# SCH_usb-hub_2024-06-19.net
KiCad netlist of a schematic drawn in EasyEDA
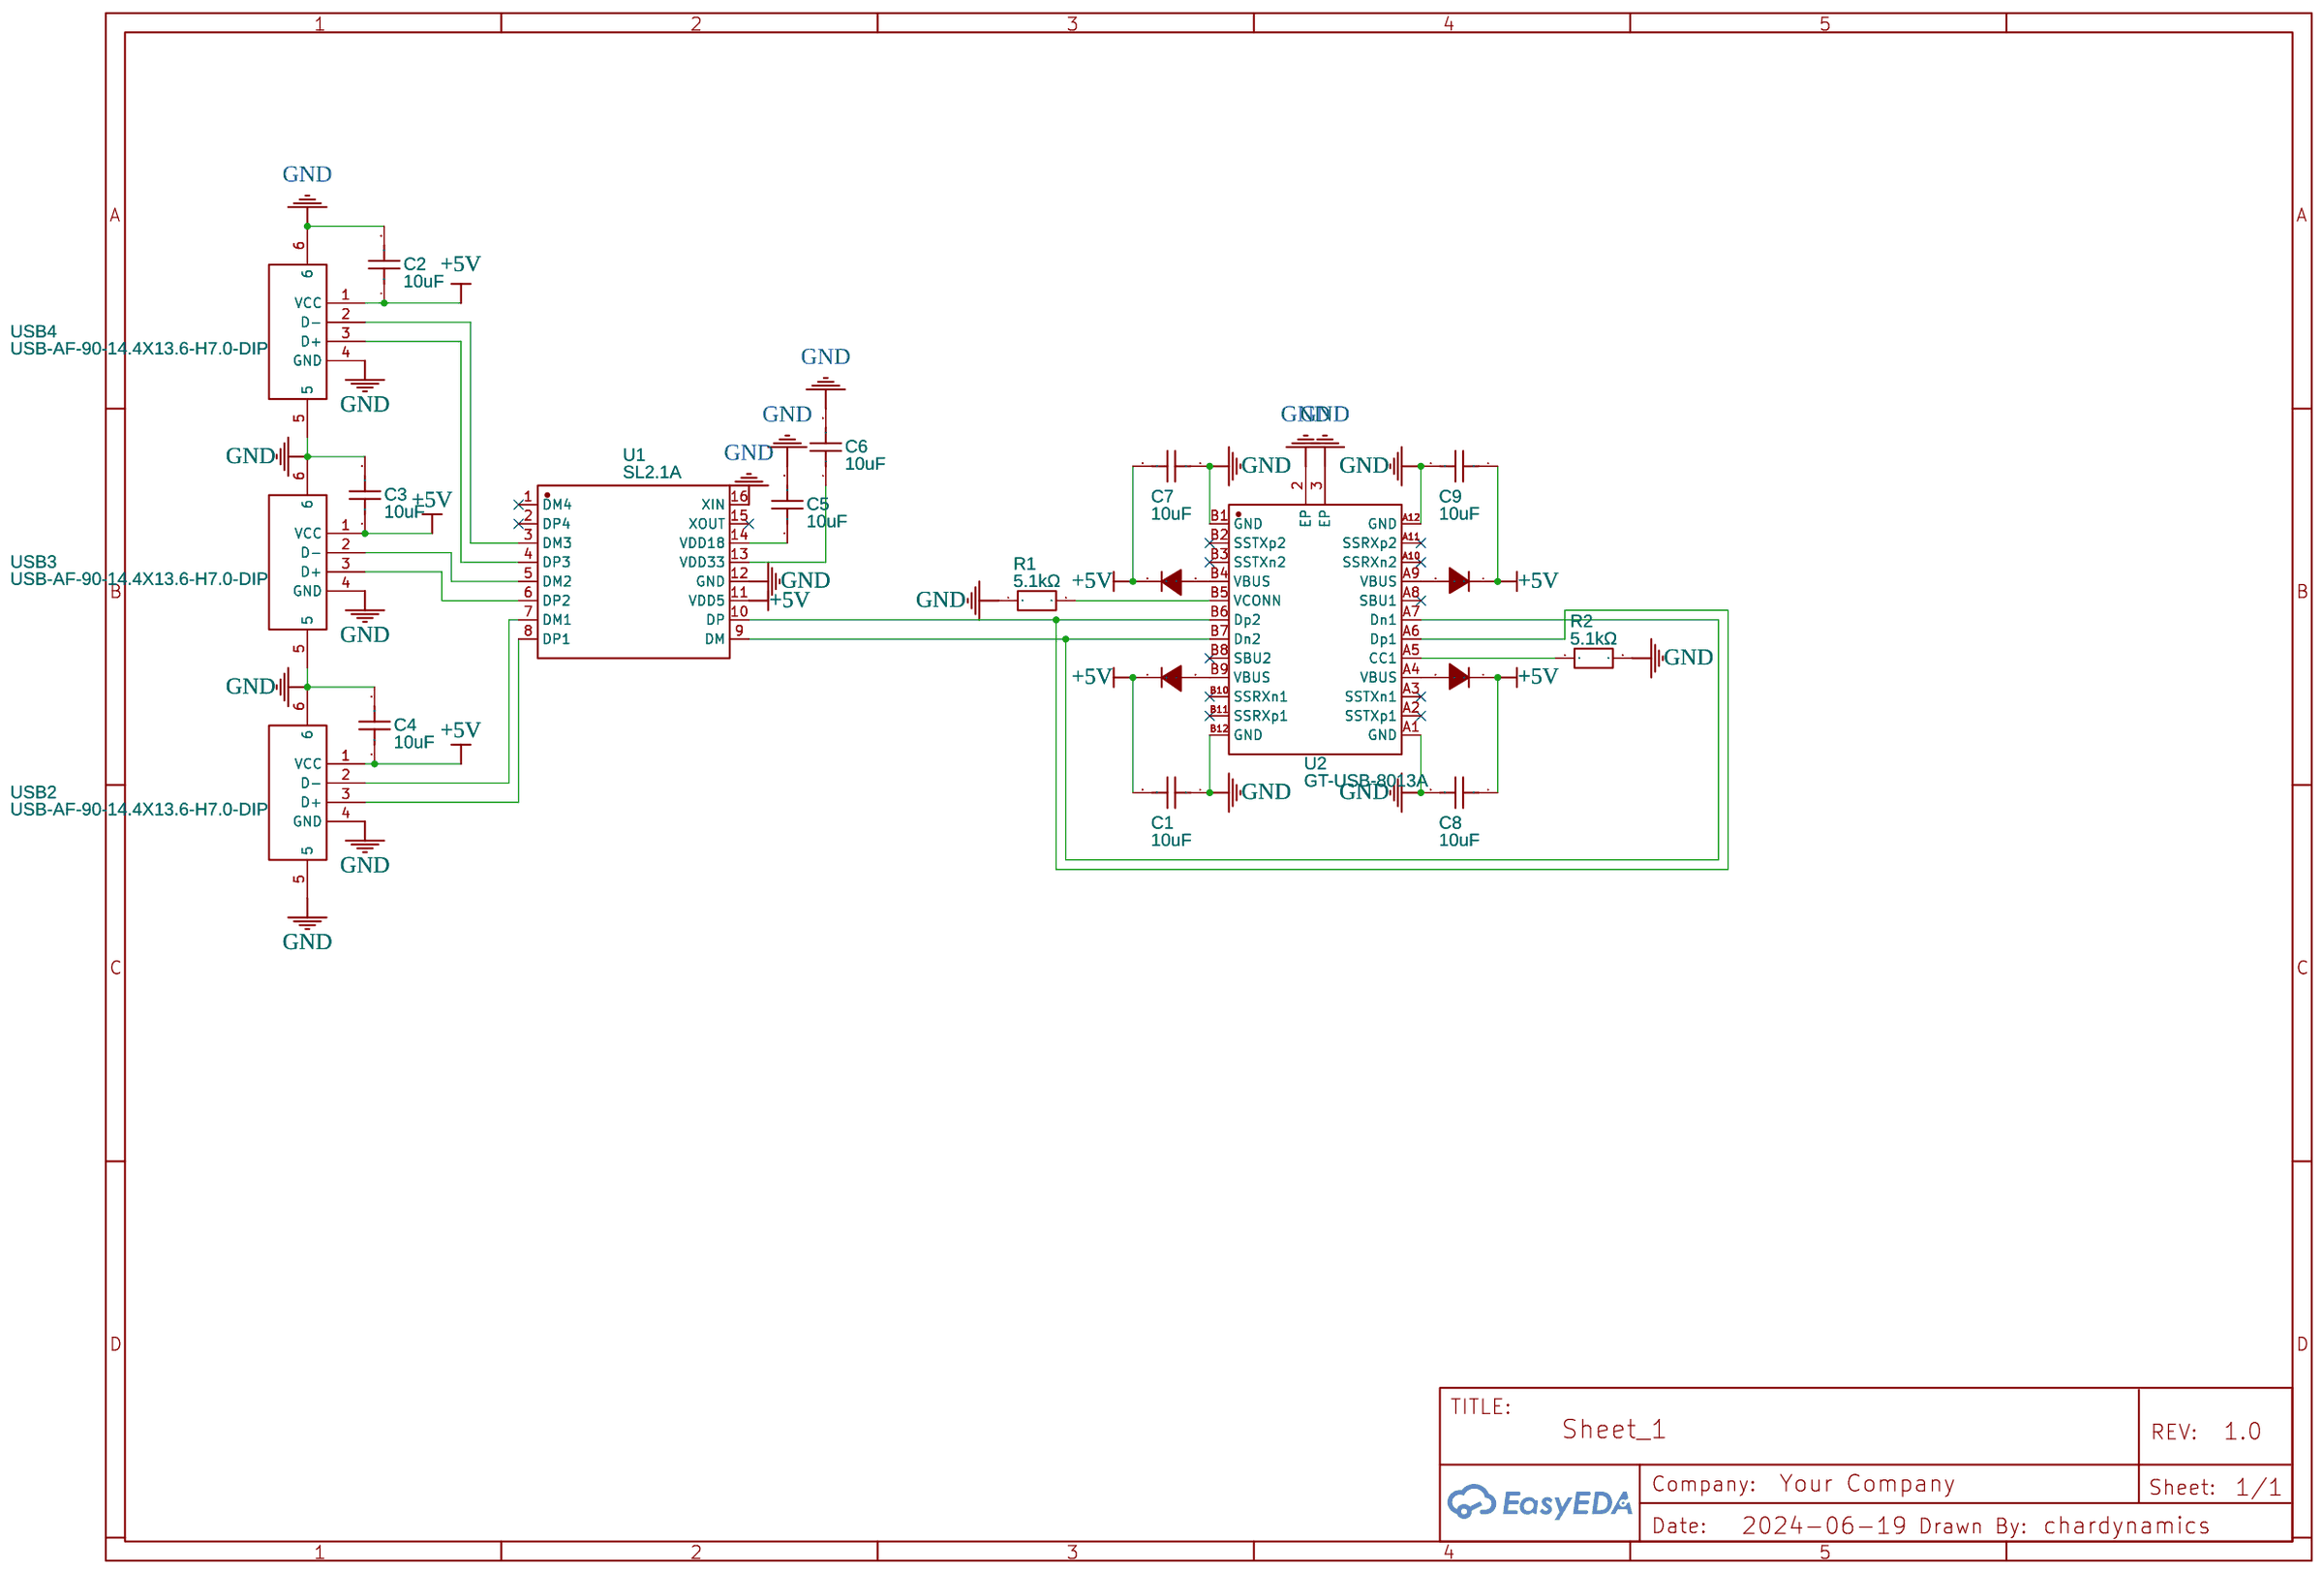
[diagram p0: schematic sheet]

(export (version "E")
  (design (tool "Eeschema 10.0.6"))
  (components
    (comp (ref "C1")
      (value "10uF")
      (fields
        (field (name "Manufacturer Part") "CL10A106KP8NNNC")
        (field (name "Manufacturer") "SAMSUNG(三星)")
      )
      (libsource (lib "") (part "CL10A106KP8NNNC_1"))
    )
    (comp (ref "C2")
      (value "10uF")
      (fields
        (field (name "Manufacturer Part") "CL10A106KP8NNNC")
        (field (name "Manufacturer") "SAMSUNG(三星)")
      )
      (libsource (lib "") (part "CL10A106KP8NNNC"))
    )
    (comp (ref "C3")
      (value "10uF")
      (fields
        (field (name "Manufacturer Part") "CL10A106KP8NNNC")
        (field (name "Manufacturer") "SAMSUNG(三星)")
      )
      (libsource (lib "") (part "CL10A106KP8NNNC"))
    )
    (comp (ref "C4")
      (value "10uF")
      (fields
        (field (name "Manufacturer Part") "CL10A106KP8NNNC")
        (field (name "Manufacturer") "SAMSUNG(三星)")
      )
      (libsource (lib "") (part "CL10A106KP8NNNC"))
    )
    (comp (ref "C5")
      (value "10uF")
      (fields
        (field (name "Manufacturer Part") "CL10A106KP8NNNC")
        (field (name "Manufacturer") "SAMSUNG(三星)")
      )
      (libsource (lib "") (part "CL10A106KP8NNNC"))
    )
    (comp (ref "C6")
      (value "10uF")
      (fields
        (field (name "Manufacturer Part") "CL10A106KP8NNNC")
        (field (name "Manufacturer") "SAMSUNG(三星)")
      )
      (libsource (lib "") (part "CL10A106KP8NNNC"))
    )
    (comp (ref "C7")
      (value "10uF")
      (fields
        (field (name "Manufacturer Part") "CL10A106KP8NNNC")
        (field (name "Manufacturer") "SAMSUNG(三星)")
      )
      (libsource (lib "") (part "CL10A106KP8NNNC_1"))
    )
    (comp (ref "C8")
      (value "10uF")
      (fields
        (field (name "Manufacturer Part") "CL10A106KP8NNNC")
        (field (name "Manufacturer") "SAMSUNG(三星)")
      )
      (libsource (lib "") (part "CL10A106KP8NNNC_1"))
    )
    (comp (ref "C9")
      (value "10uF")
      (fields
        (field (name "Manufacturer Part") "CL10A106KP8NNNC")
        (field (name "Manufacturer") "SAMSUNG(三星)")
      )
      (libsource (lib "") (part "CL10A106KP8NNNC_1"))
    )
    (comp (ref "D1")
      (value "NSR0320MW2T1G")
      (fields (field (name "Manufacturer") "onsemi(安森美)"))
      (libsource (lib "") (part "NSR0320MW2T1G"))
    )
    (comp (ref "D2")
      (value "NSR0320MW2T1G")
      (fields (field (name "Manufacturer") "onsemi(安森美)"))
      (libsource (lib "") (part "NSR0320MW2T1G_1"))
    )
    (comp (ref "D3")
      (value "NSR0320MW2T1G")
      (fields (field (name "Manufacturer") "onsemi(安森美)"))
      (libsource (lib "") (part "NSR0320MW2T1G_1"))
    )
    (comp (ref "D4")
      (value "NSR0320MW2T1G")
      (fields (field (name "Manufacturer") "onsemi(安森美)"))
      (libsource (lib "") (part "NSR0320MW2T1G"))
    )
    (comp (ref "R1")
      (value "5.1kΩ")
      (fields (field (name "Manufacturer Part") "RTT205101FTE") (field (name "Manufacturer") "RALEC(旺诠)"))
      (libsource (lib "") (part "RTT205101FTE"))
    )
    (comp (ref "R2")
      (value "5.1kΩ")
      (fields (field (name "Manufacturer Part") "RTT205101FTE") (field (name "Manufacturer") "RALEC(旺诠)"))
      (libsource (lib "") (part "RTT205101FTE"))
    )
    (comp (ref "U1")
      (value "SL2.1A")
      (fields (field (name "Manufacturer") "CoreChips(和芯润德)"))
      (libsource (lib "") (part "SL2.1A"))
    )
    (comp (ref "U2")
      (value "GT-USB-8013A")
      (fields (field (name "Manufacturer") "G-Switch(品赞)"))
      (libsource (lib "") (part "GT-USB-8013A"))
    )
    (comp (ref "USB2")
      (value "USB-AF-90-14.4X13.6-H7.0-DIP")
      (fields (field (name "Manufacturer Part") "903-131A1011D10100") (field (name "Manufacturer") "精拓金"))
      (libsource (lib "") (part "USB-AF-90-14.4X13.6-H7.0-DIP"))
    )
    (comp (ref "USB3")
      (value "USB-AF-90-14.4X13.6-H7.0-DIP")
      (fields (field (name "Manufacturer Part") "903-131A1011D10100") (field (name "Manufacturer") "精拓金"))
      (libsource (lib "") (part "USB-AF-90-14.4X13.6-H7.0-DIP"))
    )
    (comp (ref "USB4")
      (value "USB-AF-90-14.4X13.6-H7.0-DIP")
      (fields (field (name "Manufacturer Part") "903-131A1011D10100") (field (name "Manufacturer") "精拓金"))
      (libsource (lib "") (part "USB-AF-90-14.4X13.6-H7.0-DIP"))
    )
  )
  (nets
    (net (code "1") (name "+5V") (class "Default")
      (node (ref "C1") (pin "2") (pinfunction "2_2") (pintype "unspecified"))
      (node (ref "C2") (pin "1") (pinfunction "1_1") (pintype "unspecified"))
      (node (ref "C3") (pin "1") (pinfunction "1_1") (pintype "unspecified"))
      (node (ref "C4") (pin "1") (pinfunction "1_1") (pintype "unspecified"))
      (node (ref "C7") (pin "2") (pinfunction "2_2") (pintype "unspecified"))
      (node (ref "C8") (pin "1") (pinfunction "1_1") (pintype "unspecified"))
      (node (ref "C9") (pin "1") (pinfunction "1_1") (pintype "unspecified"))
      (node (ref "D1") (pin "1") (pinfunction "C_1") (pintype "unspecified"))
      (node (ref "D2") (pin "1") (pinfunction "C_1") (pintype "unspecified"))
      (node (ref "D3") (pin "1") (pinfunction "C_1") (pintype "unspecified"))
      (node (ref "D4") (pin "1") (pinfunction "C_1") (pintype "unspecified"))
      (node (ref "U1") (pin "11") (pinfunction "VDD5_11") (pintype "unspecified"))
      (node (ref "USB2") (pin "1") (pinfunction "VCC_1") (pintype "unspecified"))
      (node (ref "USB3") (pin "1") (pinfunction "VCC_1") (pintype "unspecified"))
      (node (ref "USB4") (pin "1") (pinfunction "VCC_1") (pintype "unspecified"))
    )
    (net (code "2") (name "GND") (class "Default")
      (node (ref "C1") (pin "1") (pinfunction "1_1") (pintype "unspecified"))
      (node (ref "C2") (pin "2") (pinfunction "2_2") (pintype "unspecified"))
      (node (ref "C3") (pin "2") (pinfunction "2_2") (pintype "unspecified"))
      (node (ref "C4") (pin "2") (pinfunction "2_2") (pintype "unspecified"))
      (node (ref "C5") (pin "2") (pinfunction "2_2") (pintype "unspecified"))
      (node (ref "C6") (pin "2") (pinfunction "2_2") (pintype "unspecified"))
      (node (ref "C7") (pin "1") (pinfunction "1_1") (pintype "unspecified"))
      (node (ref "C8") (pin "2") (pinfunction "2_2") (pintype "unspecified"))
      (node (ref "C9") (pin "2") (pinfunction "2_2") (pintype "unspecified"))
      (node (ref "R1") (pin "1") (pinfunction "1_1") (pintype "unspecified"))
      (node (ref "R2") (pin "2") (pinfunction "2_2") (pintype "unspecified"))
      (node (ref "U1") (pin "12") (pinfunction "GND_12") (pintype "unspecified"))
      (node (ref "U1") (pin "16") (pinfunction "XIN_16") (pintype "unspecified"))
      (node (ref "U2") (pin "2") (pinfunction "EP_2") (pintype "unspecified"))
      (node (ref "U2") (pin "3") (pinfunction "EP_3") (pintype "unspecified"))
      (node (ref "U2") (pin "A1") (pinfunction "GND_A1") (pintype "unspecified"))
      (node (ref "U2") (pin "A12") (pinfunction "GND_A12") (pintype "unspecified"))
      (node (ref "U2") (pin "B1") (pinfunction "GND_B1") (pintype "unspecified"))
      (node (ref "U2") (pin "B12") (pinfunction "GND_B12") (pintype "unspecified"))
      (node (ref "USB2") (pin "4") (pinfunction "GND_4") (pintype "unspecified"))
      (node (ref "USB2") (pin "5") (pinfunction "5_5") (pintype "unspecified"))
      (node (ref "USB2") (pin "6") (pinfunction "6_6") (pintype "unspecified"))
      (node (ref "USB3") (pin "4") (pinfunction "GND_4") (pintype "unspecified"))
      (node (ref "USB3") (pin "5") (pinfunction "5_5") (pintype "unspecified"))
      (node (ref "USB3") (pin "6") (pinfunction "6_6") (pintype "unspecified"))
      (node (ref "USB4") (pin "4") (pinfunction "GND_4") (pintype "unspecified"))
      (node (ref "USB4") (pin "5") (pinfunction "5_5") (pintype "unspecified"))
      (node (ref "USB4") (pin "6") (pinfunction "6_6") (pintype "unspecified"))
    )
    (net (code "3") (name "Net-(D1-A)") (class "Default")
      (node (ref "D1") (pin "2") (pinfunction "A_2") (pintype "unspecified"))
      (node (ref "U2") (pin "B9") (pinfunction "VBUS_B9") (pintype "unspecified"))
    )
    (net (code "4") (name "Net-(D2-A)") (class "Default")
      (node (ref "D2") (pin "2") (pinfunction "A_2") (pintype "unspecified"))
      (node (ref "U2") (pin "A9") (pinfunction "VBUS_A9") (pintype "unspecified"))
    )
    (net (code "5") (name "Net-(D3-A)") (class "Default")
      (node (ref "D3") (pin "2") (pinfunction "A_2") (pintype "unspecified"))
      (node (ref "U2") (pin "A4") (pinfunction "VBUS_A4") (pintype "unspecified"))
    )
    (net (code "6") (name "Net-(D4-A)") (class "Default")
      (node (ref "D4") (pin "2") (pinfunction "A_2") (pintype "unspecified"))
      (node (ref "U2") (pin "B4") (pinfunction "VBUS_B4") (pintype "unspecified"))
    )
    (net (code "7") (name "Net-(U1-DM)") (class "Default")
      (node (ref "U1") (pin "9") (pinfunction "DM_9") (pintype "unspecified"))
      (node (ref "U2") (pin "A7") (pinfunction "Dn1_A7") (pintype "unspecified"))
      (node (ref "U2") (pin "B7") (pinfunction "Dn2_B7") (pintype "unspecified"))
    )
    (net (code "8") (name "Net-(U1-DM1)") (class "Default")
      (node (ref "U1") (pin "7") (pinfunction "DM1_7") (pintype "unspecified"))
      (node (ref "USB2") (pin "2") (pinfunction "D-_2") (pintype "unspecified"))
    )
    (net (code "9") (name "Net-(U1-DM2)") (class "Default")
      (node (ref "U1") (pin "5") (pinfunction "DM2_5") (pintype "unspecified"))
      (node (ref "USB3") (pin "2") (pinfunction "D-_2") (pintype "unspecified"))
    )
    (net (code "10") (name "Net-(U1-DM3)") (class "Default")
      (node (ref "U1") (pin "3") (pinfunction "DM3_3") (pintype "unspecified"))
      (node (ref "USB4") (pin "2") (pinfunction "D-_2") (pintype "unspecified"))
    )
    (net (code "11") (name "Net-(U1-DP)") (class "Default")
      (node (ref "U1") (pin "10") (pinfunction "DP_10") (pintype "unspecified"))
      (node (ref "U2") (pin "A6") (pinfunction "Dp1_A6") (pintype "unspecified"))
      (node (ref "U2") (pin "B6") (pinfunction "Dp2_B6") (pintype "unspecified"))
    )
    (net (code "12") (name "Net-(U1-DP1)") (class "Default")
      (node (ref "U1") (pin "8") (pinfunction "DP1_8") (pintype "unspecified"))
      (node (ref "USB2") (pin "3") (pinfunction "D+_3") (pintype "unspecified"))
    )
    (net (code "13") (name "Net-(U1-DP2)") (class "Default")
      (node (ref "U1") (pin "6") (pinfunction "DP2_6") (pintype "unspecified"))
      (node (ref "USB3") (pin "3") (pinfunction "D+_3") (pintype "unspecified"))
    )
    (net (code "14") (name "Net-(U1-DP3)") (class "Default")
      (node (ref "U1") (pin "4") (pinfunction "DP3_4") (pintype "unspecified"))
      (node (ref "USB4") (pin "3") (pinfunction "D+_3") (pintype "unspecified"))
    )
    (net (code "15") (name "Net-(U1-VDD18)") (class "Default")
      (node (ref "C5") (pin "1") (pinfunction "1_1") (pintype "unspecified"))
      (node (ref "U1") (pin "14") (pinfunction "VDD18_14") (pintype "unspecified"))
    )
    (net (code "16") (name "Net-(U1-VDD33)") (class "Default")
      (node (ref "C6") (pin "1") (pinfunction "1_1") (pintype "unspecified"))
      (node (ref "U1") (pin "13") (pinfunction "VDD33_13") (pintype "unspecified"))
    )
    (net (code "17") (name "Net-(U2-CC1)") (class "Default")
      (node (ref "R2") (pin "1") (pinfunction "1_1") (pintype "unspecified"))
      (node (ref "U2") (pin "A5") (pinfunction "CC1_A5") (pintype "unspecified"))
    )
    (net (code "18") (name "Net-(U2-VCONN)") (class "Default")
      (node (ref "R1") (pin "2") (pinfunction "2_2") (pintype "unspecified"))
      (node (ref "U2") (pin "B5") (pinfunction "VCONN_B5") (pintype "unspecified"))
    )
    (net (code "19") (name "unconnected-(U1-DM4-Pad1)") (class "Default")
      (node (ref "U1") (pin "1") (pinfunction "DM4_1") (pintype "unspecified+no_connect"))
    )
    (net (code "20") (name "unconnected-(U1-DP4-Pad2)") (class "Default")
      (node (ref "U1") (pin "2") (pinfunction "DP4_2") (pintype "unspecified+no_connect"))
    )
    (net (code "21") (name "unconnected-(U1-XOUT-Pad15)") (class "Default")
      (node (ref "U1") (pin "15") (pinfunction "XOUT_15") (pintype "unspecified+no_connect"))
    )
    (net (code "22") (name "unconnected-(U2-SBU1-PadA8)") (class "Default")
      (node (ref "U2") (pin "A8") (pinfunction "SBU1_A8") (pintype "unspecified+no_connect"))
    )
    (net (code "23") (name "unconnected-(U2-SBU2-PadB8)") (class "Default")
      (node (ref "U2") (pin "B8") (pinfunction "SBU2_B8") (pintype "unspecified+no_connect"))
    )
    (net (code "24") (name "unconnected-(U2-SSRXn1-PadB10)") (class "Default")
      (node (ref "U2") (pin "B10") (pinfunction "SSRXn1_B10") (pintype "unspecified+no_connect"))
    )
    (net (code "25") (name "unconnected-(U2-SSRXn2-PadA10)") (class "Default")
      (node (ref "U2") (pin "A10") (pinfunction "SSRXn2_A10") (pintype "unspecified+no_connect"))
    )
    (net (code "26") (name "unconnected-(U2-SSRXp1-PadB11)") (class "Default")
      (node (ref "U2") (pin "B11") (pinfunction "SSRXp1_B11") (pintype "unspecified+no_connect"))
    )
    (net (code "27") (name "unconnected-(U2-SSRXp2-PadA11)") (class "Default")
      (node (ref "U2") (pin "A11") (pinfunction "SSRXp2_A11") (pintype "unspecified+no_connect"))
    )
    (net (code "28") (name "unconnected-(U2-SSTXn1-PadA3)") (class "Default")
      (node (ref "U2") (pin "A3") (pinfunction "SSTXn1_A3") (pintype "unspecified+no_connect"))
    )
    (net (code "29") (name "unconnected-(U2-SSTXn2-PadB3)") (class "Default")
      (node (ref "U2") (pin "B3") (pinfunction "SSTXn2_B3") (pintype "unspecified+no_connect"))
    )
    (net (code "30") (name "unconnected-(U2-SSTXp1-PadA2)") (class "Default")
      (node (ref "U2") (pin "A2") (pinfunction "SSTXp1_A2") (pintype "unspecified+no_connect"))
    )
    (net (code "31") (name "unconnected-(U2-SSTXp2-PadB2)") (class "Default")
      (node (ref "U2") (pin "B2") (pinfunction "SSTXp2_B2") (pintype "unspecified+no_connect"))
    )
  )
)
